# RobotCtrl_V2_Core-board.net
KiCad netlist of a schematic drawn in Altium Designer
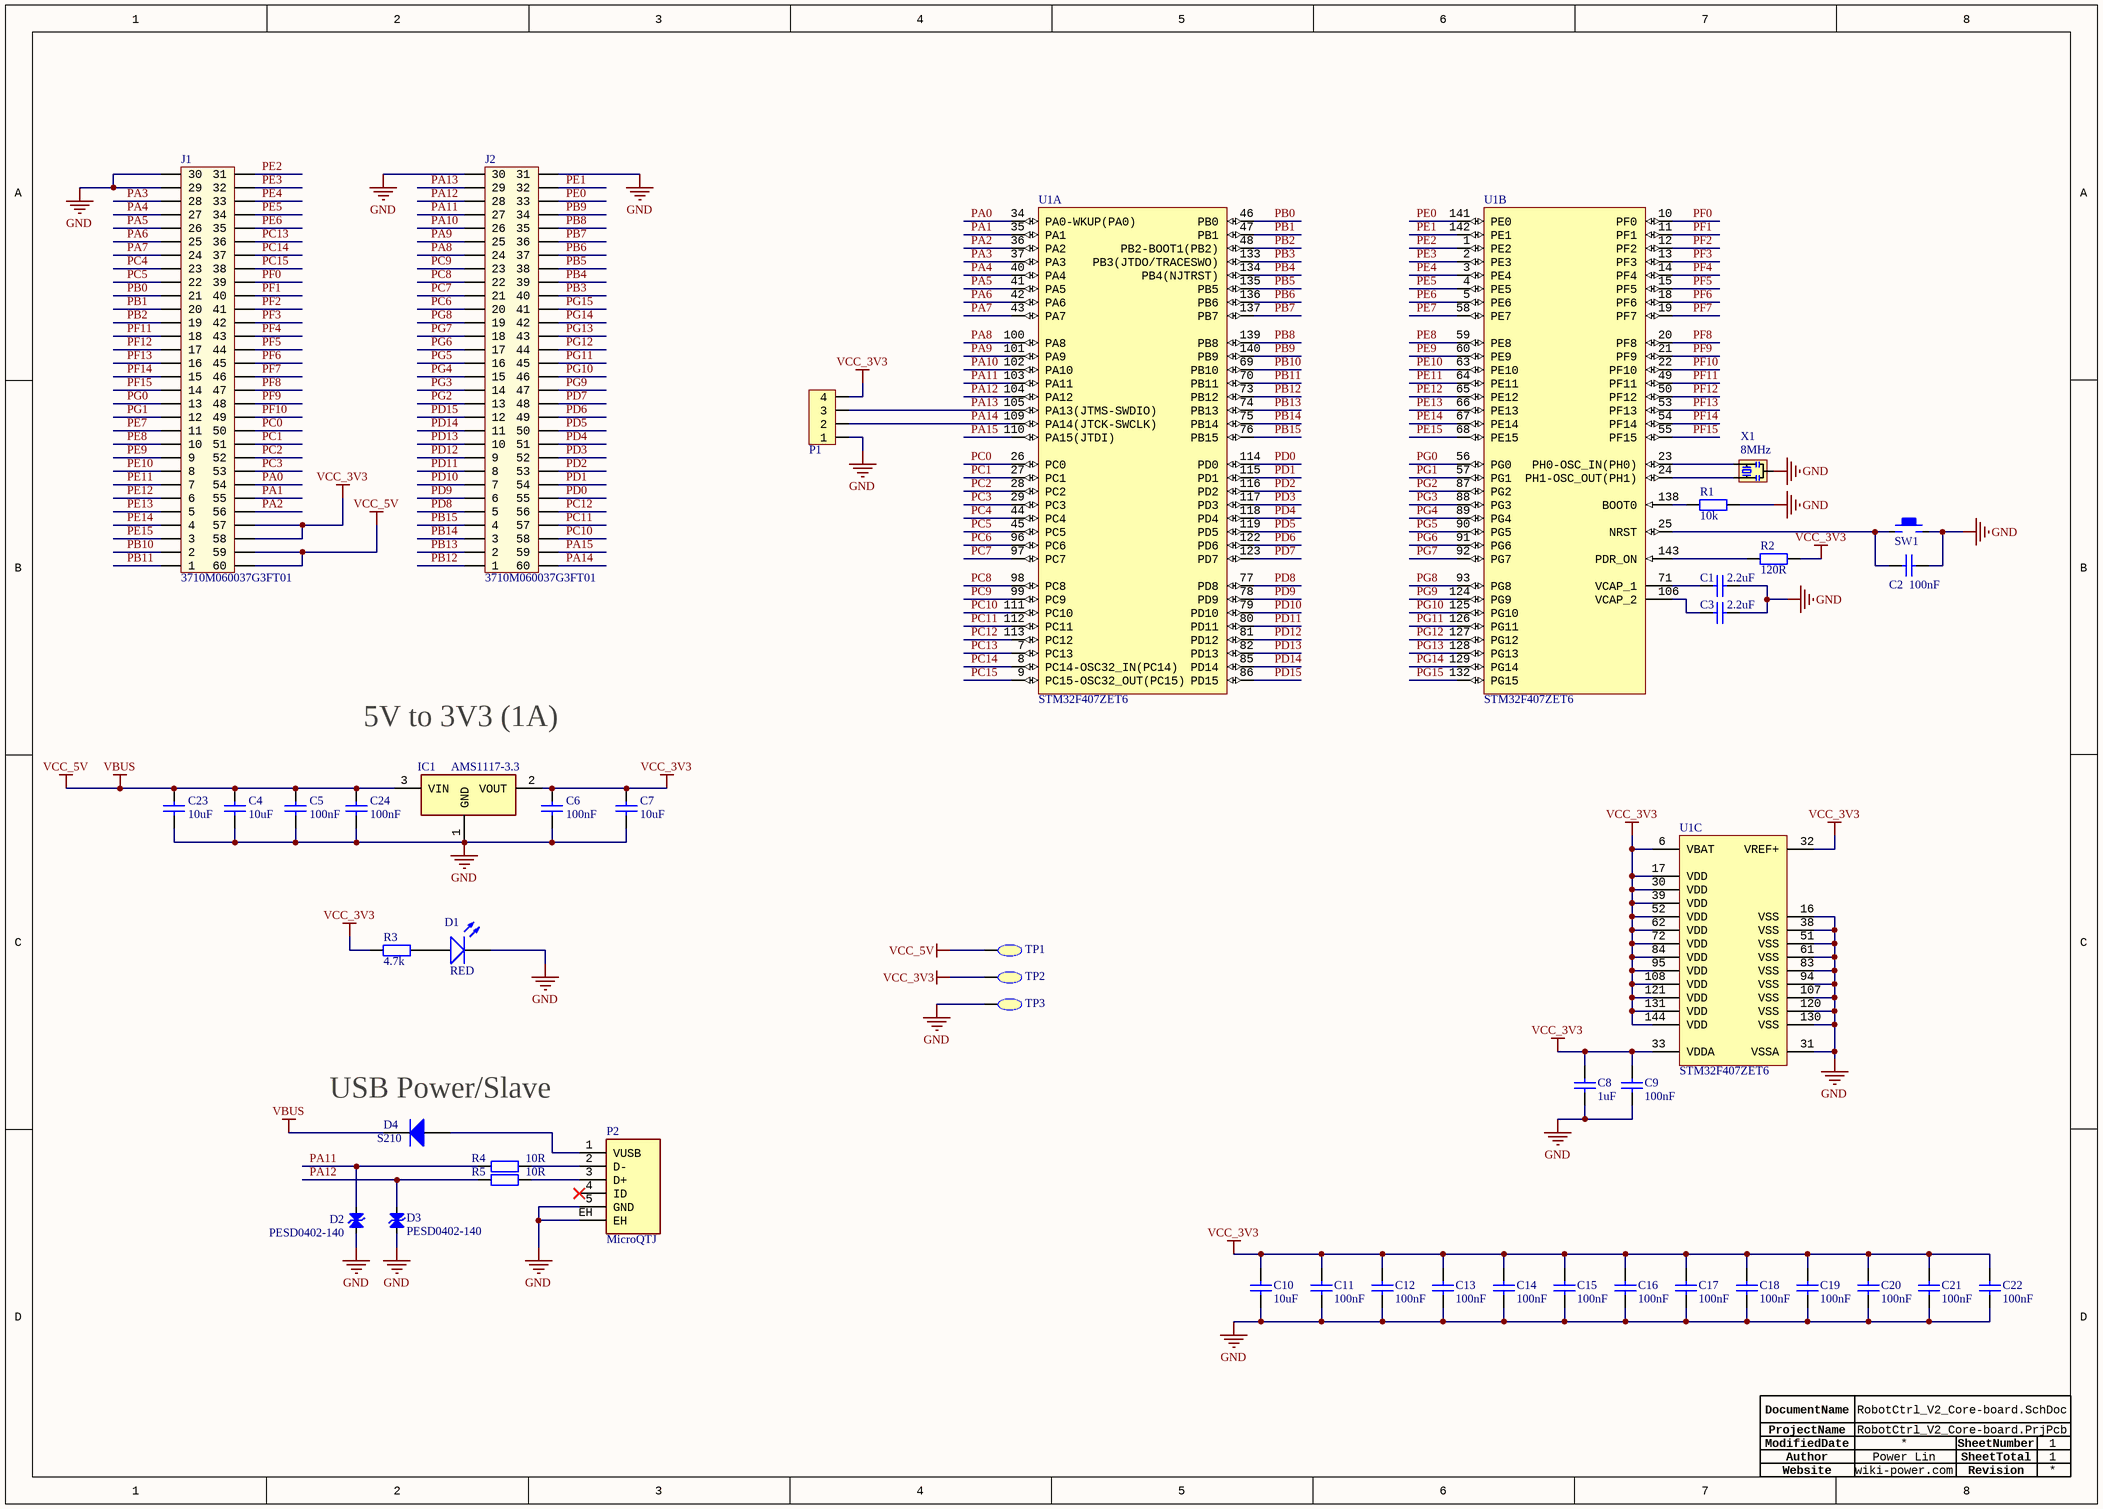
[diagram p0: RobotCtrl_V2_Core-board.SchDoc]

(export (version "E")
  (design (tool "Eeschema 10.0.6"))
  (components
    (comp (ref "C1")
      (value "2.2uF")
      (footprint "CAP-0603")
      (description "贴片电容")
      (libsource (lib "Power_Lib_Altium") (part "CAP"))
    )
    (comp (ref "C2")
      (value "100nF")
      (footprint "CAP-0603")
      (description "贴片电容")
      (libsource (lib "Power_Lib_Altium") (part "CAP"))
    )
    (comp (ref "C3")
      (value "2.2uF")
      (footprint "CAP-0603")
      (description "贴片电容")
      (libsource (lib "Power_Lib_Altium") (part "CAP"))
    )
    (comp (ref "C4")
      (value "10uF")
      (footprint "CAP-0603")
      (description "贴片电容")
      (libsource (lib "Power_Lib_Altium") (part "CAP"))
    )
    (comp (ref "C5")
      (value "100nF")
      (footprint "CAP-0603")
      (description "贴片电容")
      (libsource (lib "Power_Lib_Altium") (part "CAP"))
    )
    (comp (ref "C6")
      (value "100nF")
      (footprint "CAP-0603")
      (description "贴片电容")
      (libsource (lib "Power_Lib_Altium") (part "CAP"))
    )
    (comp (ref "C7")
      (value "10uF")
      (footprint "CAP-0603")
      (description "贴片电容")
      (libsource (lib "Power_Lib_Altium") (part "CAP"))
    )
    (comp (ref "C8")
      (value "1uF")
      (footprint "CAP-0402")
      (description "贴片电容")
      (libsource (lib "Power_Lib_Altium") (part "CAP"))
    )
    (comp (ref "C9")
      (value "100nF")
      (footprint "CAP-0402")
      (description "贴片电容")
      (libsource (lib "Power_Lib_Altium") (part "CAP"))
    )
    (comp (ref "C10")
      (value "10uF")
      (footprint "CAP-0402")
      (description "贴片电容")
      (libsource (lib "Power_Lib_Altium") (part "CAP"))
    )
    (comp (ref "C11")
      (value "100nF")
      (footprint "CAP-0402")
      (description "贴片电容")
      (libsource (lib "Power_Lib_Altium") (part "CAP"))
    )
    (comp (ref "C12")
      (value "100nF")
      (footprint "CAP-0402")
      (description "贴片电容")
      (libsource (lib "Power_Lib_Altium") (part "CAP"))
    )
    (comp (ref "C13")
      (value "100nF")
      (footprint "CAP-0402")
      (description "贴片电容")
      (libsource (lib "Power_Lib_Altium") (part "CAP"))
    )
    (comp (ref "C14")
      (value "100nF")
      (footprint "CAP-0402")
      (description "贴片电容")
      (libsource (lib "Power_Lib_Altium") (part "CAP"))
    )
    (comp (ref "C15")
      (value "100nF")
      (footprint "CAP-0402")
      (description "贴片电容")
      (libsource (lib "Power_Lib_Altium") (part "CAP"))
    )
    (comp (ref "C16")
      (value "100nF")
      (footprint "CAP-0402")
      (description "贴片电容")
      (libsource (lib "Power_Lib_Altium") (part "CAP"))
    )
    (comp (ref "C17")
      (value "100nF")
      (footprint "CAP-0402")
      (description "贴片电容")
      (libsource (lib "Power_Lib_Altium") (part "CAP"))
    )
    (comp (ref "C18")
      (value "100nF")
      (footprint "CAP-0402")
      (description "贴片电容")
      (libsource (lib "Power_Lib_Altium") (part "CAP"))
    )
    (comp (ref "C19")
      (value "100nF")
      (footprint "CAP-0402")
      (description "贴片电容")
      (libsource (lib "Power_Lib_Altium") (part "CAP"))
    )
    (comp (ref "C20")
      (value "100nF")
      (footprint "CAP-0402")
      (description "贴片电容")
      (libsource (lib "Power_Lib_Altium") (part "CAP"))
    )
    (comp (ref "C21")
      (value "100nF")
      (footprint "CAP-0402")
      (description "贴片电容")
      (libsource (lib "Power_Lib_Altium") (part "CAP"))
    )
    (comp (ref "C22")
      (value "100nF")
      (footprint "CAP-0402")
      (description "贴片电容")
      (libsource (lib "Power_Lib_Altium") (part "CAP"))
    )
    (comp (ref "C23")
      (value "10uF")
      (footprint "CAP-0603")
      (description "贴片电容")
      (libsource (lib "Power_Lib_Altium") (part "CAP"))
    )
    (comp (ref "C24")
      (value "100nF")
      (footprint "CAP-0603")
      (description "贴片电容")
      (libsource (lib "Power_Lib_Altium") (part "CAP"))
    )
    (comp (ref "D1")
      (value "RED")
      (footprint "LED-0603")
      (description "发光二极管")
      (libsource (lib "Power_Lib_Altium") (part "LED"))
    )
    (comp (ref "D2")
      (value "PESD0402-140")
      (footprint "D-0402")
      (libsource (lib "Power_Lib_Altium") (part "TVS_C"))
    )
    (comp (ref "D3")
      (value "PESD0402-140")
      (footprint "D-0402")
      (libsource (lib "Power_Lib_Altium") (part "TVS_C"))
    )
    (comp (ref "D4")
      (value "S210")
      (footprint "DO-214AA/SMB")
      (description "二极管")
      (libsource (lib "Power_Lib_Altium") (part "DIODE"))
    )
    (comp (ref "IC1")
      (value "AMS1117-3.3")
      (footprint "SOT-223")
      (description "AMS1117-3.3 1.0A")
      (fields (field (name "MANUFACTURER_PART_NUMBER") "SI2302DS") (field (name "RS PART NUMBER") "7983053P"))
      (libsource (lib "Power_Lib_Altium") (part "AMS1117"))
    )
    (comp (ref "J1")
      (value "3710M060037G3FT01")
      (footprint "3710M060037G3FT01")
      (description "B2B Connector")
      (libsource (lib "Power_Lib_Altium") (part "3710M/F"))
    )
    (comp (ref "J2")
      (value "3710M060037G3FT01")
      (footprint "3710M060037G3FT01")
      (description "B2B Connector")
      (libsource (lib "Power_Lib_Altium") (part "3710M/F"))
    )
    (comp (ref "P1")
      (value "HDR1x4_2.54")
      (footprint "HDR1X4_2.54")
      (description "Header")
      (libsource (lib "Power_Lib_Altium") (part "HDR1x4_2.54"))
    )
    (comp (ref "P2")
      (value "MicroQTJ")
      (footprint "USB-MICRO")
      (description "USB_MICRO")
      (libsource (lib "Power_Lib_Altium") (part "USB_MICRO"))
    )
    (comp (ref "R1")
      (value "10k")
      (footprint "R-0603")
      (description "贴片电阻")
      (libsource (lib "Power_Lib_Altium") (part "RES"))
    )
    (comp (ref "R2")
      (value "120R")
      (footprint "R-0603")
      (description "贴片电阻")
      (libsource (lib "Power_Lib_Altium") (part "RES"))
    )
    (comp (ref "R3")
      (value "4.7k")
      (footprint "R-0603")
      (description "贴片电阻")
      (libsource (lib "Power_Lib_Altium") (part "RES"))
    )
    (comp (ref "R4")
      (value "10R")
      (footprint "R-0603")
      (description "贴片电阻")
      (libsource (lib "") (part "RES_1"))
    )
    (comp (ref "R5")
      (value "10R")
      (footprint "R-0603")
      (description "贴片电阻")
      (libsource (lib "") (part "RES_1"))
    )
    (comp (ref "SW1")
      (value "KEY")
      (footprint "KEY-4P-4.2*3.4*2.5")
      (description "按键开关")
      (libsource (lib "Power_Lib_Altium") (part "KEY"))
    )
    (comp (ref "TP1")
      (value "TestPoint")
      (footprint "TestPoint")
      (description "测试点")
      (libsource (lib "Power_Lib_Altium") (part "TestPoint"))
    )
    (comp (ref "TP2")
      (value "TestPoint")
      (footprint "TestPoint")
      (description "测试点")
      (libsource (lib "Power_Lib_Altium") (part "TestPoint"))
    )
    (comp (ref "TP3")
      (value "TestPoint")
      (footprint "TestPoint")
      (description "测试点")
      (libsource (lib "Power_Lib_Altium") (part "TestPoint"))
    )
    (comp (ref "U1")
      (value "STM32F407ZET6")
      (footprint "STM-LQFP144_N")
      (fields (field (name "MANUFACTURER") "STMicroelectronics"))
      (libsource (lib "Power_Lib_Altium") (part "STM32F407ZET6"))
    )
    (comp (ref "X1")
      (value "8MHz")
      (footprint "SMD3213-3P")
      (description "CSTCE8M00G15C99-R0")
      (libsource (lib "Power_Lib_Altium") (part "XTAL"))
    )
  )
  (nets
    (net (code "1") (name "/PA0") (class "Default")
      (node (ref "J1") (pin "54") (pinfunction "54_54") (pintype "passive"))
      (node (ref "U1") (pin "34") (pinfunction "PA0-WKUP(PA0)_34") (pintype "bidirectional"))
    )
    (net (code "2") (name "/PA1") (class "Default")
      (node (ref "J1") (pin "55") (pinfunction "55_55") (pintype "passive"))
      (node (ref "U1") (pin "35") (pinfunction "PA1_35") (pintype "bidirectional"))
    )
    (net (code "3") (name "/PA2") (class "Default")
      (node (ref "J1") (pin "56") (pinfunction "56_56") (pintype "passive"))
      (node (ref "U1") (pin "36") (pinfunction "PA2_36") (pintype "bidirectional"))
    )
    (net (code "4") (name "/PA3") (class "Default")
      (node (ref "J1") (pin "28") (pinfunction "28_28") (pintype "passive"))
      (node (ref "U1") (pin "37") (pinfunction "PA3_37") (pintype "bidirectional"))
    )
    (net (code "5") (name "/PA4") (class "Default")
      (node (ref "J1") (pin "27") (pinfunction "27_27") (pintype "passive"))
      (node (ref "U1") (pin "40") (pinfunction "PA4_40") (pintype "bidirectional"))
    )
    (net (code "6") (name "/PA5") (class "Default")
      (node (ref "J1") (pin "26") (pinfunction "26_26") (pintype "passive"))
      (node (ref "U1") (pin "41") (pinfunction "PA5_41") (pintype "bidirectional"))
    )
    (net (code "7") (name "/PA6") (class "Default")
      (node (ref "J1") (pin "25") (pinfunction "25_25") (pintype "passive"))
      (node (ref "U1") (pin "42") (pinfunction "PA6_42") (pintype "bidirectional"))
    )
    (net (code "8") (name "/PA7") (class "Default")
      (node (ref "J1") (pin "24") (pinfunction "24_24") (pintype "passive"))
      (node (ref "U1") (pin "43") (pinfunction "PA7_43") (pintype "bidirectional"))
    )
    (net (code "9") (name "/PA8") (class "Default")
      (node (ref "J2") (pin "24") (pinfunction "24_24") (pintype "passive"))
      (node (ref "U1") (pin "100") (pinfunction "PA8_100") (pintype "bidirectional"))
    )
    (net (code "10") (name "/PA9") (class "Default")
      (node (ref "J2") (pin "25") (pinfunction "25_25") (pintype "passive"))
      (node (ref "U1") (pin "101") (pinfunction "PA9_101") (pintype "bidirectional"))
    )
    (net (code "11") (name "/PA10") (class "Default")
      (node (ref "J2") (pin "26") (pinfunction "26_26") (pintype "passive"))
      (node (ref "U1") (pin "102") (pinfunction "PA10_102") (pintype "bidirectional"))
    )
    (net (code "12") (name "/PA11") (class "Default")
      (node (ref "D2") (pin "2") (pinfunction "2_2") (pintype "passive"))
      (node (ref "J2") (pin "27") (pinfunction "27_27") (pintype "passive"))
      (node (ref "R4") (pin "1") (pinfunction "1_1") (pintype "passive"))
      (node (ref "U1") (pin "103") (pinfunction "PA11_103") (pintype "bidirectional"))
    )
    (net (code "13") (name "/PA12") (class "Default")
      (node (ref "D3") (pin "2") (pinfunction "2_2") (pintype "passive"))
      (node (ref "J2") (pin "28") (pinfunction "28_28") (pintype "passive"))
      (node (ref "R5") (pin "1") (pinfunction "1_1") (pintype "passive"))
      (node (ref "U1") (pin "104") (pinfunction "PA12_104") (pintype "bidirectional"))
    )
    (net (code "14") (name "/PA13") (class "Default")
      (node (ref "J2") (pin "29") (pinfunction "29_29") (pintype "passive"))
      (node (ref "P1") (pin "3") (pinfunction "3_3") (pintype "passive"))
      (node (ref "U1") (pin "105") (pinfunction "PA13(JTMS-SWDIO)_105") (pintype "bidirectional"))
    )
    (net (code "15") (name "/PA14") (class "Default")
      (node (ref "J2") (pin "60") (pinfunction "60_60") (pintype "passive"))
      (node (ref "P1") (pin "2") (pinfunction "2_2") (pintype "passive"))
      (node (ref "U1") (pin "109") (pinfunction "PA14(JTCK-SWCLK)_109") (pintype "bidirectional"))
    )
    (net (code "16") (name "/PA15") (class "Default")
      (node (ref "J2") (pin "59") (pinfunction "59_59") (pintype "passive"))
      (node (ref "U1") (pin "110") (pinfunction "PA15(JTDI)_110") (pintype "bidirectional"))
    )
    (net (code "17") (name "/PB0") (class "Default")
      (node (ref "J1") (pin "21") (pinfunction "21_21") (pintype "passive"))
      (node (ref "U1") (pin "46") (pinfunction "PB0_46") (pintype "bidirectional"))
    )
    (net (code "18") (name "/PB1") (class "Default")
      (node (ref "J1") (pin "20") (pinfunction "20_20") (pintype "passive"))
      (node (ref "U1") (pin "47") (pinfunction "PB1_47") (pintype "bidirectional"))
    )
    (net (code "19") (name "/PB2") (class "Default")
      (node (ref "J1") (pin "19") (pinfunction "19_19") (pintype "passive"))
      (node (ref "U1") (pin "48") (pinfunction "PB2-BOOT1(PB2)_48") (pintype "bidirectional"))
    )
    (net (code "20") (name "/PB3") (class "Default")
      (node (ref "J2") (pin "40") (pinfunction "40_40") (pintype "passive"))
      (node (ref "U1") (pin "133") (pinfunction "PB3(JTDO/TRACESWO)_133") (pintype "bidirectional"))
    )
    (net (code "21") (name "/PB4") (class "Default")
      (node (ref "J2") (pin "39") (pinfunction "39_39") (pintype "passive"))
      (node (ref "U1") (pin "134") (pinfunction "PB4(NJTRST)_134") (pintype "bidirectional"))
    )
    (net (code "22") (name "/PB5") (class "Default")
      (node (ref "J2") (pin "38") (pinfunction "38_38") (pintype "passive"))
      (node (ref "U1") (pin "135") (pinfunction "PB5_135") (pintype "bidirectional"))
    )
    (net (code "23") (name "/PB6") (class "Default")
      (node (ref "J2") (pin "37") (pinfunction "37_37") (pintype "passive"))
      (node (ref "U1") (pin "136") (pinfunction "PB6_136") (pintype "bidirectional"))
    )
    (net (code "24") (name "/PB7") (class "Default")
      (node (ref "J2") (pin "36") (pinfunction "36_36") (pintype "passive"))
      (node (ref "U1") (pin "137") (pinfunction "PB7_137") (pintype "bidirectional"))
    )
    (net (code "25") (name "/PB8") (class "Default")
      (node (ref "J2") (pin "35") (pinfunction "35_35") (pintype "passive"))
      (node (ref "U1") (pin "139") (pinfunction "PB8_139") (pintype "bidirectional"))
    )
    (net (code "26") (name "/PB9") (class "Default")
      (node (ref "J2") (pin "34") (pinfunction "34_34") (pintype "passive"))
      (node (ref "U1") (pin "140") (pinfunction "PB9_140") (pintype "bidirectional"))
    )
    (net (code "27") (name "/PB10") (class "Default")
      (node (ref "J1") (pin "2") (pinfunction "2_2") (pintype "passive"))
      (node (ref "U1") (pin "69") (pinfunction "PB10_69") (pintype "bidirectional"))
    )
    (net (code "28") (name "/PB11") (class "Default")
      (node (ref "J1") (pin "1") (pinfunction "1_1") (pintype "passive"))
      (node (ref "U1") (pin "70") (pinfunction "PB11_70") (pintype "bidirectional"))
    )
    (net (code "29") (name "/PB12") (class "Default")
      (node (ref "J2") (pin "1") (pinfunction "1_1") (pintype "passive"))
      (node (ref "U1") (pin "73") (pinfunction "PB12_73") (pintype "bidirectional"))
    )
    (net (code "30") (name "/PB13") (class "Default")
      (node (ref "J2") (pin "2") (pinfunction "2_2") (pintype "passive"))
      (node (ref "U1") (pin "74") (pinfunction "PB13_74") (pintype "bidirectional"))
    )
    (net (code "31") (name "/PB14") (class "Default")
      (node (ref "J2") (pin "3") (pinfunction "3_3") (pintype "passive"))
      (node (ref "U1") (pin "75") (pinfunction "PB14_75") (pintype "bidirectional"))
    )
    (net (code "32") (name "/PB15") (class "Default")
      (node (ref "J2") (pin "4") (pinfunction "4_4") (pintype "passive"))
      (node (ref "U1") (pin "76") (pinfunction "PB15_76") (pintype "bidirectional"))
    )
    (net (code "33") (name "/PC0") (class "Default")
      (node (ref "J1") (pin "50") (pinfunction "50_50") (pintype "passive"))
      (node (ref "U1") (pin "26") (pinfunction "PC0_26") (pintype "bidirectional"))
    )
    (net (code "34") (name "/PC1") (class "Default")
      (node (ref "J1") (pin "51") (pinfunction "51_51") (pintype "passive"))
      (node (ref "U1") (pin "27") (pinfunction "PC1_27") (pintype "bidirectional"))
    )
    (net (code "35") (name "/PC2") (class "Default")
      (node (ref "J1") (pin "52") (pinfunction "52_52") (pintype "passive"))
      (node (ref "U1") (pin "28") (pinfunction "PC2_28") (pintype "bidirectional"))
    )
    (net (code "36") (name "/PC3") (class "Default")
      (node (ref "J1") (pin "53") (pinfunction "53_53") (pintype "passive"))
      (node (ref "U1") (pin "29") (pinfunction "PC3_29") (pintype "bidirectional"))
    )
    (net (code "37") (name "/PC4") (class "Default")
      (node (ref "J1") (pin "23") (pinfunction "23_23") (pintype "passive"))
      (node (ref "U1") (pin "44") (pinfunction "PC4_44") (pintype "bidirectional"))
    )
    (net (code "38") (name "/PC5") (class "Default")
      (node (ref "J1") (pin "22") (pinfunction "22_22") (pintype "passive"))
      (node (ref "U1") (pin "45") (pinfunction "PC5_45") (pintype "bidirectional"))
    )
    (net (code "39") (name "/PC6") (class "Default")
      (node (ref "J2") (pin "20") (pinfunction "20_20") (pintype "passive"))
      (node (ref "U1") (pin "96") (pinfunction "PC6_96") (pintype "bidirectional"))
    )
    (net (code "40") (name "/PC7") (class "Default")
      (node (ref "J2") (pin "21") (pinfunction "21_21") (pintype "passive"))
      (node (ref "U1") (pin "97") (pinfunction "PC7_97") (pintype "bidirectional"))
    )
    (net (code "41") (name "/PC8") (class "Default")
      (node (ref "J2") (pin "22") (pinfunction "22_22") (pintype "passive"))
      (node (ref "U1") (pin "98") (pinfunction "PC8_98") (pintype "bidirectional"))
    )
    (net (code "42") (name "/PC9") (class "Default")
      (node (ref "J2") (pin "23") (pinfunction "23_23") (pintype "passive"))
      (node (ref "U1") (pin "99") (pinfunction "PC9_99") (pintype "bidirectional"))
    )
    (net (code "43") (name "/PC10") (class "Default")
      (node (ref "J2") (pin "58") (pinfunction "58_58") (pintype "passive"))
      (node (ref "U1") (pin "111") (pinfunction "PC10_111") (pintype "bidirectional"))
    )
    (net (code "44") (name "/PC11") (class "Default")
      (node (ref "J2") (pin "57") (pinfunction "57_57") (pintype "passive"))
      (node (ref "U1") (pin "112") (pinfunction "PC11_112") (pintype "bidirectional"))
    )
    (net (code "45") (name "/PC12") (class "Default")
      (node (ref "J2") (pin "56") (pinfunction "56_56") (pintype "passive"))
      (node (ref "U1") (pin "113") (pinfunction "PC12_113") (pintype "bidirectional"))
    )
    (net (code "46") (name "/PC13") (class "Default")
      (node (ref "J1") (pin "36") (pinfunction "36_36") (pintype "passive"))
      (node (ref "U1") (pin "7") (pinfunction "PC13_7") (pintype "bidirectional"))
    )
    (net (code "47") (name "/PC14") (class "Default")
      (node (ref "J1") (pin "37") (pinfunction "37_37") (pintype "passive"))
      (node (ref "U1") (pin "8") (pinfunction "PC14-OSC32_IN(PC14)_8") (pintype "bidirectional"))
    )
    (net (code "48") (name "/PC15") (class "Default")
      (node (ref "J1") (pin "38") (pinfunction "38_38") (pintype "passive"))
      (node (ref "U1") (pin "9") (pinfunction "PC15-OSC32_OUT(PC15)_9") (pintype "bidirectional"))
    )
    (net (code "49") (name "/PD0") (class "Default")
      (node (ref "J2") (pin "55") (pinfunction "55_55") (pintype "passive"))
      (node (ref "U1") (pin "114") (pinfunction "PD0_114") (pintype "bidirectional"))
    )
    (net (code "50") (name "/PD1") (class "Default")
      (node (ref "J2") (pin "54") (pinfunction "54_54") (pintype "passive"))
      (node (ref "U1") (pin "115") (pinfunction "PD1_115") (pintype "bidirectional"))
    )
    (net (code "51") (name "/PD2") (class "Default")
      (node (ref "J2") (pin "53") (pinfunction "53_53") (pintype "passive"))
      (node (ref "U1") (pin "116") (pinfunction "PD2_116") (pintype "bidirectional"))
    )
    (net (code "52") (name "/PD3") (class "Default")
      (node (ref "J2") (pin "52") (pinfunction "52_52") (pintype "passive"))
      (node (ref "U1") (pin "117") (pinfunction "PD3_117") (pintype "bidirectional"))
    )
    (net (code "53") (name "/PD4") (class "Default")
      (node (ref "J2") (pin "51") (pinfunction "51_51") (pintype "passive"))
      (node (ref "U1") (pin "118") (pinfunction "PD4_118") (pintype "bidirectional"))
    )
    (net (code "54") (name "/PD5") (class "Default")
      (node (ref "J2") (pin "50") (pinfunction "50_50") (pintype "passive"))
      (node (ref "U1") (pin "119") (pinfunction "PD5_119") (pintype "bidirectional"))
    )
    (net (code "55") (name "/PD6") (class "Default")
      (node (ref "J2") (pin "49") (pinfunction "49_49") (pintype "passive"))
      (node (ref "U1") (pin "122") (pinfunction "PD6_122") (pintype "bidirectional"))
    )
    (net (code "56") (name "/PD7") (class "Default")
      (node (ref "J2") (pin "48") (pinfunction "48_48") (pintype "passive"))
      (node (ref "U1") (pin "123") (pinfunction "PD7_123") (pintype "bidirectional"))
    )
    (net (code "57") (name "/PD8") (class "Default")
      (node (ref "J2") (pin "5") (pinfunction "5_5") (pintype "passive"))
      (node (ref "U1") (pin "77") (pinfunction "PD8_77") (pintype "bidirectional"))
    )
    (net (code "58") (name "/PD9") (class "Default")
      (node (ref "J2") (pin "6") (pinfunction "6_6") (pintype "passive"))
      (node (ref "U1") (pin "78") (pinfunction "PD9_78") (pintype "bidirectional"))
    )
    (net (code "59") (name "/PD10") (class "Default")
      (node (ref "J2") (pin "7") (pinfunction "7_7") (pintype "passive"))
      (node (ref "U1") (pin "79") (pinfunction "PD10_79") (pintype "bidirectional"))
    )
    (net (code "60") (name "/PD11") (class "Default")
      (node (ref "J2") (pin "8") (pinfunction "8_8") (pintype "passive"))
      (node (ref "U1") (pin "80") (pinfunction "PD11_80") (pintype "bidirectional"))
    )
    (net (code "61") (name "/PD12") (class "Default")
      (node (ref "J2") (pin "9") (pinfunction "9_9") (pintype "passive"))
      (node (ref "U1") (pin "81") (pinfunction "PD12_81") (pintype "bidirectional"))
    )
    (net (code "62") (name "/PD13") (class "Default")
      (node (ref "J2") (pin "10") (pinfunction "10_10") (pintype "passive"))
      (node (ref "U1") (pin "82") (pinfunction "PD13_82") (pintype "bidirectional"))
    )
    (net (code "63") (name "/PD14") (class "Default")
      (node (ref "J2") (pin "11") (pinfunction "11_11") (pintype "passive"))
      (node (ref "U1") (pin "85") (pinfunction "PD14_85") (pintype "bidirectional"))
    )
    (net (code "64") (name "/PD15") (class "Default")
      (node (ref "J2") (pin "12") (pinfunction "12_12") (pintype "passive"))
      (node (ref "U1") (pin "86") (pinfunction "PD15_86") (pintype "bidirectional"))
    )
    (net (code "65") (name "/PE0") (class "Default")
      (node (ref "J2") (pin "33") (pinfunction "33_33") (pintype "passive"))
      (node (ref "U1") (pin "141") (pinfunction "PE0_141") (pintype "bidirectional"))
    )
    (net (code "66") (name "/PE1") (class "Default")
      (node (ref "J2") (pin "32") (pinfunction "32_32") (pintype "passive"))
      (node (ref "U1") (pin "142") (pinfunction "PE1_142") (pintype "bidirectional"))
    )
    (net (code "67") (name "/PE2") (class "Default")
      (node (ref "J1") (pin "31") (pinfunction "31_31") (pintype "passive"))
      (node (ref "U1") (pin "1") (pinfunction "PE2_1") (pintype "bidirectional"))
    )
    (net (code "68") (name "/PE3") (class "Default")
      (node (ref "J1") (pin "32") (pinfunction "32_32") (pintype "passive"))
      (node (ref "U1") (pin "2") (pinfunction "PE3_2") (pintype "bidirectional"))
    )
    (net (code "69") (name "/PE4") (class "Default")
      (node (ref "J1") (pin "33") (pinfunction "33_33") (pintype "passive"))
      (node (ref "U1") (pin "3") (pinfunction "PE4_3") (pintype "bidirectional"))
    )
    (net (code "70") (name "/PE5") (class "Default")
      (node (ref "J1") (pin "34") (pinfunction "34_34") (pintype "passive"))
      (node (ref "U1") (pin "4") (pinfunction "PE5_4") (pintype "bidirectional"))
    )
    (net (code "71") (name "/PE6") (class "Default")
      (node (ref "J1") (pin "35") (pinfunction "35_35") (pintype "passive"))
      (node (ref "U1") (pin "5") (pinfunction "PE6_5") (pintype "bidirectional"))
    )
    (net (code "72") (name "/PE7") (class "Default")
      (node (ref "J1") (pin "11") (pinfunction "11_11") (pintype "passive"))
      (node (ref "U1") (pin "58") (pinfunction "PE7_58") (pintype "bidirectional"))
    )
    (net (code "73") (name "/PE8") (class "Default")
      (node (ref "J1") (pin "10") (pinfunction "10_10") (pintype "passive"))
      (node (ref "U1") (pin "59") (pinfunction "PE8_59") (pintype "bidirectional"))
    )
    (net (code "74") (name "/PE9") (class "Default")
      (node (ref "J1") (pin "9") (pinfunction "9_9") (pintype "passive"))
      (node (ref "U1") (pin "60") (pinfunction "PE9_60") (pintype "bidirectional"))
    )
    (net (code "75") (name "/PE10") (class "Default")
      (node (ref "J1") (pin "8") (pinfunction "8_8") (pintype "passive"))
      (node (ref "U1") (pin "63") (pinfunction "PE10_63") (pintype "bidirectional"))
    )
    (net (code "76") (name "/PE11") (class "Default")
      (node (ref "J1") (pin "7") (pinfunction "7_7") (pintype "passive"))
      (node (ref "U1") (pin "64") (pinfunction "PE11_64") (pintype "bidirectional"))
    )
    (net (code "77") (name "/PE12") (class "Default")
      (node (ref "J1") (pin "6") (pinfunction "6_6") (pintype "passive"))
      (node (ref "U1") (pin "65") (pinfunction "PE12_65") (pintype "bidirectional"))
    )
    (net (code "78") (name "/PE13") (class "Default")
      (node (ref "J1") (pin "5") (pinfunction "5_5") (pintype "passive"))
      (node (ref "U1") (pin "66") (pinfunction "PE13_66") (pintype "bidirectional"))
    )
    (net (code "79") (name "/PE14") (class "Default")
      (node (ref "J1") (pin "4") (pinfunction "4_4") (pintype "passive"))
      (node (ref "U1") (pin "67") (pinfunction "PE14_67") (pintype "bidirectional"))
    )
    (net (code "80") (name "/PE15") (class "Default")
      (node (ref "J1") (pin "3") (pinfunction "3_3") (pintype "passive"))
      (node (ref "U1") (pin "68") (pinfunction "PE15_68") (pintype "bidirectional"))
    )
    (net (code "81") (name "/PF0") (class "Default")
      (node (ref "J1") (pin "39") (pinfunction "39_39") (pintype "passive"))
      (node (ref "U1") (pin "10") (pinfunction "PF0_10") (pintype "bidirectional"))
    )
    (net (code "82") (name "/PF1") (class "Default")
      (node (ref "J1") (pin "40") (pinfunction "40_40") (pintype "passive"))
      (node (ref "U1") (pin "11") (pinfunction "PF1_11") (pintype "bidirectional"))
    )
    (net (code "83") (name "/PF2") (class "Default")
      (node (ref "J1") (pin "41") (pinfunction "41_41") (pintype "passive"))
      (node (ref "U1") (pin "12") (pinfunction "PF2_12") (pintype "bidirectional"))
    )
    (net (code "84") (name "/PF3") (class "Default")
      (node (ref "J1") (pin "42") (pinfunction "42_42") (pintype "passive"))
      (node (ref "U1") (pin "13") (pinfunction "PF3_13") (pintype "bidirectional"))
    )
    (net (code "85") (name "/PF4") (class "Default")
      (node (ref "J1") (pin "43") (pinfunction "43_43") (pintype "passive"))
      (node (ref "U1") (pin "14") (pinfunction "PF4_14") (pintype "bidirectional"))
    )
    (net (code "86") (name "/PF5") (class "Default")
      (node (ref "J1") (pin "44") (pinfunction "44_44") (pintype "passive"))
      (node (ref "U1") (pin "15") (pinfunction "PF5_15") (pintype "bidirectional"))
    )
    (net (code "87") (name "/PF6") (class "Default")
      (node (ref "J1") (pin "45") (pinfunction "45_45") (pintype "passive"))
      (node (ref "U1") (pin "18") (pinfunction "PF6_18") (pintype "bidirectional"))
    )
    (net (code "88") (name "/PF7") (class "Default")
      (node (ref "J1") (pin "46") (pinfunction "46_46") (pintype "passive"))
      (node (ref "U1") (pin "19") (pinfunction "PF7_19") (pintype "bidirectional"))
    )
    (net (code "89") (name "/PF8") (class "Default")
      (node (ref "J1") (pin "47") (pinfunction "47_47") (pintype "passive"))
      (node (ref "U1") (pin "20") (pinfunction "PF8_20") (pintype "bidirectional"))
    )
    (net (code "90") (name "/PF9") (class "Default")
      (node (ref "J1") (pin "48") (pinfunction "48_48") (pintype "passive"))
      (node (ref "U1") (pin "21") (pinfunction "PF9_21") (pintype "bidirectional"))
    )
    (net (code "91") (name "/PF10") (class "Default")
      (node (ref "J1") (pin "49") (pinfunction "49_49") (pintype "passive"))
      (node (ref "U1") (pin "22") (pinfunction "PF10_22") (pintype "bidirectional"))
    )
    (net (code "92") (name "/PF11") (class "Default")
      (node (ref "J1") (pin "18") (pinfunction "18_18") (pintype "passive"))
      (node (ref "U1") (pin "49") (pinfunction "PF11_49") (pintype "bidirectional"))
    )
    (net (code "93") (name "/PF12") (class "Default")
      (node (ref "J1") (pin "17") (pinfunction "17_17") (pintype "passive"))
      (node (ref "U1") (pin "50") (pinfunction "PF12_50") (pintype "bidirectional"))
    )
    (net (code "94") (name "/PF13") (class "Default")
      (node (ref "J1") (pin "16") (pinfunction "16_16") (pintype "passive"))
      (node (ref "U1") (pin "53") (pinfunction "PF13_53") (pintype "bidirectional"))
    )
    (net (code "95") (name "/PF14") (class "Default")
      (node (ref "J1") (pin "15") (pinfunction "15_15") (pintype "passive"))
      (node (ref "U1") (pin "54") (pinfunction "PF14_54") (pintype "bidirectional"))
    )
    (net (code "96") (name "/PF15") (class "Default")
      (node (ref "J1") (pin "14") (pinfunction "14_14") (pintype "passive"))
      (node (ref "U1") (pin "55") (pinfunction "PF15_55") (pintype "bidirectional"))
    )
    (net (code "97") (name "/PG0") (class "Default")
      (node (ref "J1") (pin "13") (pinfunction "13_13") (pintype "passive"))
      (node (ref "U1") (pin "56") (pinfunction "PG0_56") (pintype "bidirectional"))
    )
    (net (code "98") (name "/PG1") (class "Default")
      (node (ref "J1") (pin "12") (pinfunction "12_12") (pintype "passive"))
      (node (ref "U1") (pin "57") (pinfunction "PG1_57") (pintype "bidirectional"))
    )
    (net (code "99") (name "/PG2") (class "Default")
      (node (ref "J2") (pin "13") (pinfunction "13_13") (pintype "passive"))
      (node (ref "U1") (pin "87") (pinfunction "PG2_87") (pintype "bidirectional"))
    )
    (net (code "100") (name "/PG3") (class "Default")
      (node (ref "J2") (pin "14") (pinfunction "14_14") (pintype "passive"))
      (node (ref "U1") (pin "88") (pinfunction "PG3_88") (pintype "bidirectional"))
    )
    (net (code "101") (name "/PG4") (class "Default")
      (node (ref "J2") (pin "15") (pinfunction "15_15") (pintype "passive"))
      (node (ref "U1") (pin "89") (pinfunction "PG4_89") (pintype "bidirectional"))
    )
    (net (code "102") (name "/PG5") (class "Default")
      (node (ref "J2") (pin "16") (pinfunction "16_16") (pintype "passive"))
      (node (ref "U1") (pin "90") (pinfunction "PG5_90") (pintype "bidirectional"))
    )
    (net (code "103") (name "/PG6") (class "Default")
      (node (ref "J2") (pin "17") (pinfunction "17_17") (pintype "passive"))
      (node (ref "U1") (pin "91") (pinfunction "PG6_91") (pintype "bidirectional"))
    )
    (net (code "104") (name "/PG7") (class "Default")
      (node (ref "J2") (pin "18") (pinfunction "18_18") (pintype "passive"))
      (node (ref "U1") (pin "92") (pinfunction "PG7_92") (pintype "bidirectional"))
    )
    (net (code "105") (name "/PG8") (class "Default")
      (node (ref "J2") (pin "19") (pinfunction "19_19") (pintype "passive"))
      (node (ref "U1") (pin "93") (pinfunction "PG8_93") (pintype "bidirectional"))
    )
    (net (code "106") (name "/PG9") (class "Default")
      (node (ref "J2") (pin "47") (pinfunction "47_47") (pintype "passive"))
      (node (ref "U1") (pin "124") (pinfunction "PG9_124") (pintype "bidirectional"))
    )
    (net (code "107") (name "/PG10") (class "Default")
      (node (ref "J2") (pin "46") (pinfunction "46_46") (pintype "passive"))
      (node (ref "U1") (pin "125") (pinfunction "PG10_125") (pintype "bidirectional"))
    )
    (net (code "108") (name "/PG11") (class "Default")
      (node (ref "J2") (pin "45") (pinfunction "45_45") (pintype "passive"))
      (node (ref "U1") (pin "126") (pinfunction "PG11_126") (pintype "bidirectional"))
    )
    (net (code "109") (name "/PG12") (class "Default")
      (node (ref "J2") (pin "44") (pinfunction "44_44") (pintype "passive"))
      (node (ref "U1") (pin "127") (pinfunction "PG12_127") (pintype "bidirectional"))
    )
    (net (code "110") (name "/PG13") (class "Default")
      (node (ref "J2") (pin "43") (pinfunction "43_43") (pintype "passive"))
      (node (ref "U1") (pin "128") (pinfunction "PG13_128") (pintype "bidirectional"))
    )
    (net (code "111") (name "/PG14") (class "Default")
      (node (ref "J2") (pin "42") (pinfunction "42_42") (pintype "passive"))
      (node (ref "U1") (pin "129") (pinfunction "PG14_129") (pintype "bidirectional"))
    )
    (net (code "112") (name "/PG15") (class "Default")
      (node (ref "J2") (pin "41") (pinfunction "41_41") (pintype "passive"))
      (node (ref "U1") (pin "132") (pinfunction "PG15_132") (pintype "bidirectional"))
    )
    (net (code "113") (name "GND") (class "Default")
      (node (ref "C1") (pin "2") (pinfunction "2_2") (pintype "passive"))
      (node (ref "C10") (pin "1") (pinfunction "1_1") (pintype "passive"))
      (node (ref "C11") (pin "1") (pinfunction "1_1") (pintype "passive"))
      (node (ref "C12") (pin "1") (pinfunction "1_1") (pintype "passive"))
      (node (ref "C13") (pin "1") (pinfunction "1_1") (pintype "passive"))
      (node (ref "C14") (pin "1") (pinfunction "1_1") (pintype "passive"))
      (node (ref "C15") (pin "1") (pinfunction "1_1") (pintype "passive"))
      (node (ref "C16") (pin "1") (pinfunction "1_1") (pintype "passive"))
      (node (ref "C17") (pin "1") (pinfunction "1_1") (pintype "passive"))
      (node (ref "C18") (pin "1") (pinfunction "1_1") (pintype "passive"))
      (node (ref "C19") (pin "1") (pinfunction "1_1") (pintype "passive"))
      (node (ref "C2") (pin "1") (pinfunction "1_1") (pintype "passive"))
      (node (ref "C20") (pin "1") (pinfunction "1_1") (pintype "passive"))
      (node (ref "C21") (pin "1") (pinfunction "1_1") (pintype "passive"))
      (node (ref "C22") (pin "1") (pinfunction "1_1") (pintype "passive"))
      (node (ref "C23") (pin "1") (pinfunction "1_1") (pintype "passive"))
      (node (ref "C24") (pin "1") (pinfunction "1_1") (pintype "passive"))
      (node (ref "C3") (pin "2") (pinfunction "2_2") (pintype "passive"))
      (node (ref "C4") (pin "1") (pinfunction "1_1") (pintype "passive"))
      (node (ref "C5") (pin "1") (pinfunction "1_1") (pintype "passive"))
      (node (ref "C6") (pin "1") (pinfunction "1_1") (pintype "passive"))
      (node (ref "C7") (pin "1") (pinfunction "1_1") (pintype "passive"))
      (node (ref "C8") (pin "1") (pinfunction "1_1") (pintype "passive"))
      (node (ref "C9") (pin "1") (pinfunction "1_1") (pintype "passive"))
      (node (ref "D1") (pin "K") (pinfunction "K_K") (pintype "passive"))
      (node (ref "D2") (pin "1") (pinfunction "1_1") (pintype "passive"))
      (node (ref "D3") (pin "1") (pinfunction "1_1") (pintype "passive"))
      (node (ref "IC1") (pin "1") (pinfunction "GND_1") (pintype "passive"))
      (node (ref "J1") (pin "29") (pinfunction "29_29") (pintype "passive"))
      (node (ref "J1") (pin "30") (pinfunction "30_30") (pintype "passive"))
      (node (ref "J2") (pin "30") (pinfunction "30_30") (pintype "passive"))
      (node (ref "J2") (pin "31") (pinfunction "31_31") (pintype "passive"))
      (node (ref "P1") (pin "1") (pinfunction "1_1") (pintype "passive"))
      (node (ref "P2") (pin "5") (pinfunction "GND_5") (pintype "passive"))
      (node (ref "P2") (pin "EH") (pinfunction "EH_EH") (pintype "passive"))
      (node (ref "R1") (pin "1") (pinfunction "1_1") (pintype "passive"))
      (node (ref "SW1") (pin "2") (pinfunction "2_2") (pintype "passive"))
      (node (ref "TP3") (pin "1") (pinfunction "1_1") (pintype "passive"))
      (node (ref "U1") (pin "107") (pinfunction "VSS_107") (pintype "power_in"))
      (node (ref "U1") (pin "120") (pinfunction "VSS_120") (pintype "power_in"))
      (node (ref "U1") (pin "130") (pinfunction "VSS_130") (pintype "power_in"))
      (node (ref "U1") (pin "16") (pinfunction "VSS_16") (pintype "power_in"))
      (node (ref "U1") (pin "31") (pinfunction "VSSA_31") (pintype "power_in"))
      (node (ref "U1") (pin "38") (pinfunction "VSS_38") (pintype "power_in"))
      (node (ref "U1") (pin "51") (pinfunction "VSS_51") (pintype "power_in"))
      (node (ref "U1") (pin "61") (pinfunction "VSS_61") (pintype "power_in"))
      (node (ref "U1") (pin "83") (pinfunction "VSS_83") (pintype "power_in"))
      (node (ref "U1") (pin "94") (pinfunction "VSS_94") (pintype "power_in"))
      (node (ref "X1") (pin "2") (pinfunction "GND_2") (pintype "passive"))
    )
    (net (code "114") (name "Net-(D1-PadA)") (class "Default")
      (node (ref "D1") (pin "A") (pinfunction "A_A") (pintype "passive"))
      (node (ref "R3") (pin "1") (pinfunction "1_1") (pintype "passive"))
    )
    (net (code "115") (name "Net-(D4-A)") (class "Default")
      (node (ref "D4") (pin "1") (pinfunction "A_1") (pintype "passive"))
      (node (ref "P2") (pin "1") (pinfunction "VUSB_1") (pintype "passive"))
    )
    (net (code "116") (name "Net-(P2-D+)") (class "Default")
      (node (ref "P2") (pin "3") (pinfunction "D+_3") (pintype "passive"))
      (node (ref "R5") (pin "2") (pinfunction "2_2") (pintype "passive"))
    )
    (net (code "117") (name "Net-(P2-D-)") (class "Default")
      (node (ref "P2") (pin "2") (pinfunction "D-_2") (pintype "passive"))
      (node (ref "R4") (pin "2") (pinfunction "2_2") (pintype "passive"))
    )
    (net (code "118") (name "Net-(U1B-BOOT0)") (class "Default")
      (node (ref "R1") (pin "2") (pinfunction "2_2") (pintype "passive"))
      (node (ref "U1") (pin "138") (pinfunction "BOOT0_138") (pintype "input"))
    )
    (net (code "119") (name "Net-(U1B-NRST)") (class "Default")
      (node (ref "C2") (pin "2") (pinfunction "2_2") (pintype "passive"))
      (node (ref "SW1") (pin "1") (pinfunction "1_1") (pintype "passive"))
      (node (ref "U1") (pin "25") (pinfunction "NRST_25") (pintype "bidirectional"))
    )
    (net (code "120") (name "Net-(U1B-PDR_ON)") (class "Default")
      (node (ref "R2") (pin "2") (pinfunction "2_2") (pintype "passive"))
      (node (ref "U1") (pin "143") (pinfunction "PDR_ON_143") (pintype "input"))
    )
    (net (code "121") (name "Net-(U1B-PH0-OSC_IN(PH0))") (class "Default")
      (node (ref "U1") (pin "23") (pinfunction "PH0-OSC_IN(PH0)_23") (pintype "bidirectional"))
      (node (ref "X1") (pin "3") (pinfunction "OSC2_3") (pintype "passive"))
    )
    (net (code "122") (name "Net-(U1B-PH1-OSC_OUT(PH1))") (class "Default")
      (node (ref "U1") (pin "24") (pinfunction "PH1-OSC_OUT(PH1)_24") (pintype "bidirectional"))
      (node (ref "X1") (pin "1") (pinfunction "OSC1_1") (pintype "passive"))
    )
    (net (code "123") (name "Net-(U1B-VCAP_1)") (class "Default")
      (node (ref "C1") (pin "1") (pinfunction "1_1") (pintype "passive"))
      (node (ref "U1") (pin "71") (pinfunction "VCAP_1_71") (pintype "power_in"))
    )
    (net (code "124") (name "Net-(U1B-VCAP_2)") (class "Default")
      (node (ref "C3") (pin "1") (pinfunction "1_1") (pintype "passive"))
      (node (ref "U1") (pin "106") (pinfunction "VCAP_2_106") (pintype "power_in"))
    )
    (net (code "125") (name "VBUS") (class "Default")
      (node (ref "C23") (pin "2") (pinfunction "2_2") (pintype "passive"))
      (node (ref "C24") (pin "2") (pinfunction "2_2") (pintype "passive"))
      (node (ref "C4") (pin "2") (pinfunction "2_2") (pintype "passive"))
      (node (ref "C5") (pin "2") (pinfunction "2_2") (pintype "passive"))
      (node (ref "D4") (pin "2") (pinfunction "K_2") (pintype "passive"))
      (node (ref "IC1") (pin "3") (pinfunction "VIN_3") (pintype "passive"))
      (node (ref "J1") (pin "59") (pinfunction "59_59") (pintype "passive"))
      (node (ref "J1") (pin "60") (pinfunction "60_60") (pintype "passive"))
      (node (ref "TP1") (pin "1") (pinfunction "1_1") (pintype "passive"))
    )
    (net (code "126") (name "VCC_3V3") (class "Default")
      (node (ref "C10") (pin "2") (pinfunction "2_2") (pintype "passive"))
      (node (ref "C11") (pin "2") (pinfunction "2_2") (pintype "passive"))
      (node (ref "C12") (pin "2") (pinfunction "2_2") (pintype "passive"))
      (node (ref "C13") (pin "2") (pinfunction "2_2") (pintype "passive"))
      (node (ref "C14") (pin "2") (pinfunction "2_2") (pintype "passive"))
      (node (ref "C15") (pin "2") (pinfunction "2_2") (pintype "passive"))
      (node (ref "C16") (pin "2") (pinfunction "2_2") (pintype "passive"))
      (node (ref "C17") (pin "2") (pinfunction "2_2") (pintype "passive"))
      (node (ref "C18") (pin "2") (pinfunction "2_2") (pintype "passive"))
      (node (ref "C19") (pin "2") (pinfunction "2_2") (pintype "passive"))
      (node (ref "C20") (pin "2") (pinfunction "2_2") (pintype "passive"))
      (node (ref "C21") (pin "2") (pinfunction "2_2") (pintype "passive"))
      (node (ref "C22") (pin "2") (pinfunction "2_2") (pintype "passive"))
      (node (ref "C6") (pin "2") (pinfunction "2_2") (pintype "passive"))
      (node (ref "C7") (pin "2") (pinfunction "2_2") (pintype "passive"))
      (node (ref "C8") (pin "2") (pinfunction "2_2") (pintype "passive"))
      (node (ref "C9") (pin "2") (pinfunction "2_2") (pintype "passive"))
      (node (ref "IC1") (pin "2") (pinfunction "VOUT_2") (pintype "passive"))
      (node (ref "J1") (pin "57") (pinfunction "57_57") (pintype "passive"))
      (node (ref "J1") (pin "58") (pinfunction "58_58") (pintype "passive"))
      (node (ref "P1") (pin "4") (pinfunction "4_4") (pintype "passive"))
      (node (ref "R2") (pin "1") (pinfunction "1_1") (pintype "passive"))
      (node (ref "R3") (pin "2") (pinfunction "2_2") (pintype "passive"))
      (node (ref "TP2") (pin "1") (pinfunction "1_1") (pintype "passive"))
      (node (ref "U1") (pin "108") (pinfunction "VDD_108") (pintype "power_in"))
      (node (ref "U1") (pin "121") (pinfunction "VDD_121") (pintype "power_in"))
      (node (ref "U1") (pin "131") (pinfunction "VDD_131") (pintype "power_in"))
      (node (ref "U1") (pin "144") (pinfunction "VDD_144") (pintype "power_in"))
      (node (ref "U1") (pin "17") (pinfunction "VDD_17") (pintype "power_in"))
      (node (ref "U1") (pin "30") (pinfunction "VDD_30") (pintype "power_in"))
      (node (ref "U1") (pin "32") (pinfunction "VREF+_32") (pintype "power_in"))
      (node (ref "U1") (pin "33") (pinfunction "VDDA_33") (pintype "power_in"))
      (node (ref "U1") (pin "39") (pinfunction "VDD_39") (pintype "power_in"))
      (node (ref "U1") (pin "52") (pinfunction "VDD_52") (pintype "power_in"))
      (node (ref "U1") (pin "6") (pinfunction "VBAT_6") (pintype "power_in"))
      (node (ref "U1") (pin "62") (pinfunction "VDD_62") (pintype "power_in"))
      (node (ref "U1") (pin "72") (pinfunction "VDD_72") (pintype "power_in"))
      (node (ref "U1") (pin "84") (pinfunction "VDD_84") (pintype "power_in"))
      (node (ref "U1") (pin "95") (pinfunction "VDD_95") (pintype "power_in"))
    )
    (net (code "127") (name "unconnected-(P2-ID-Pad4)") (class "Default")
      (node (ref "P2") (pin "4") (pinfunction "ID_4") (pintype "passive+no_connect"))
    )
  )
)
